# haasoscope_pro_power_board.net
KiCad netlist of a schematic drawn in EAGLE
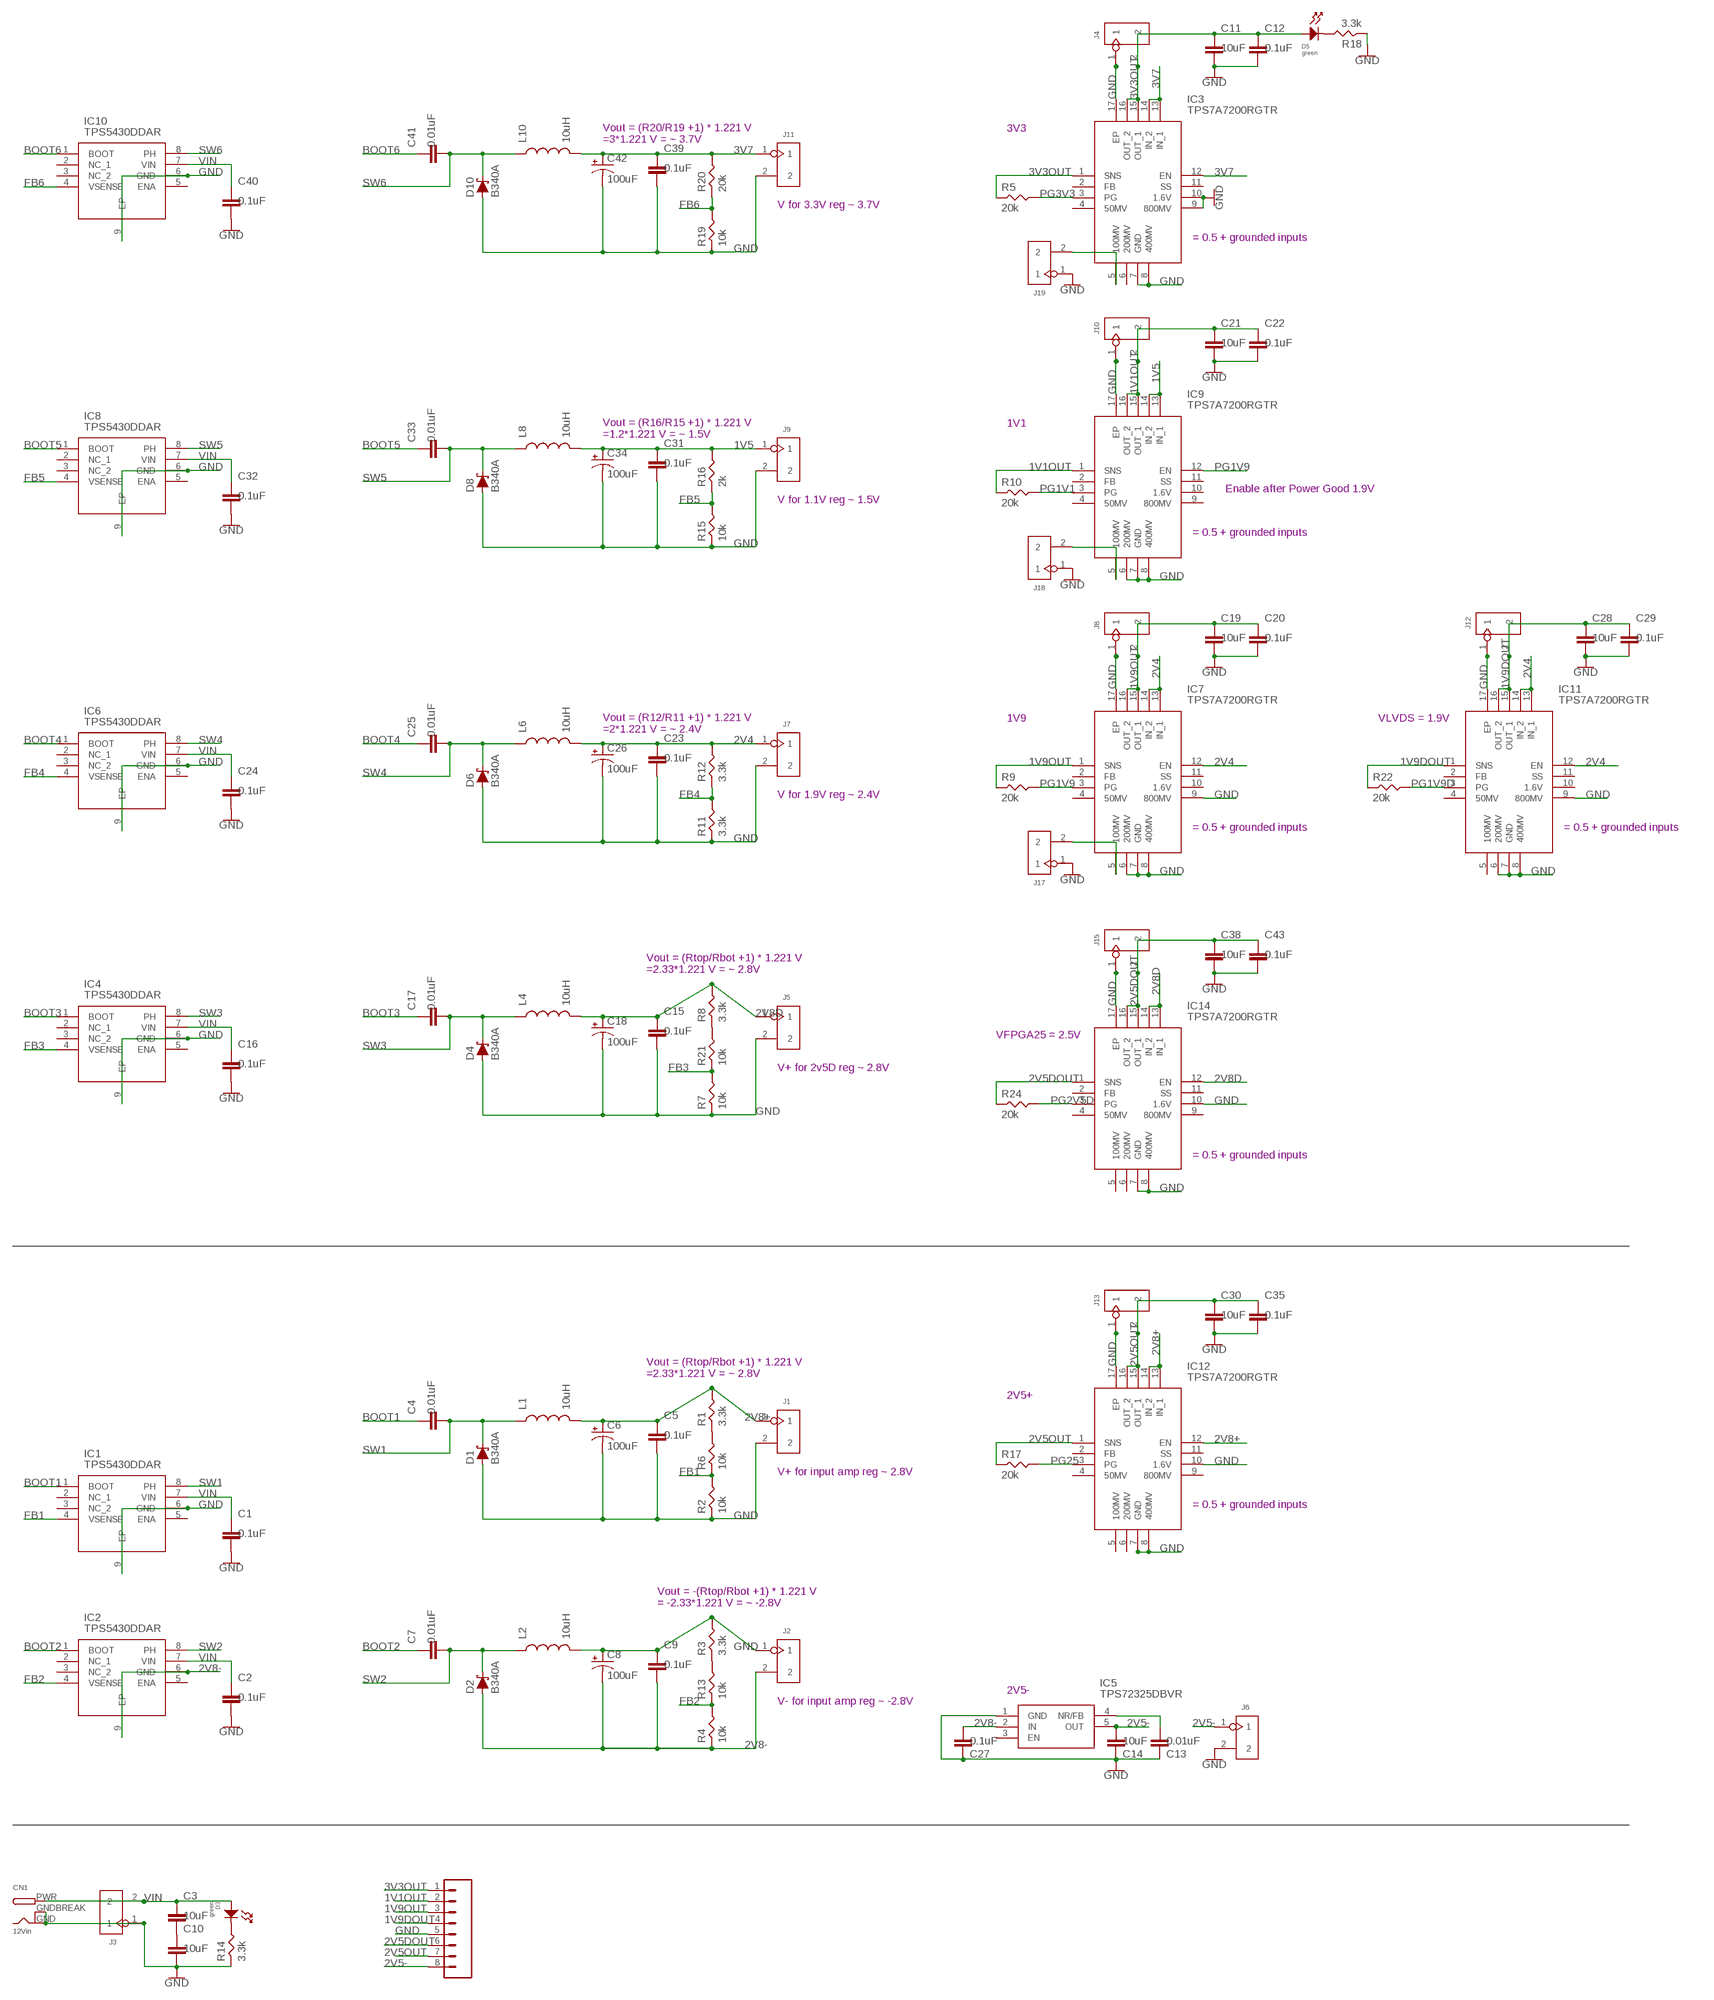
[diagram p0: schematic, sheet 1]

(export (version "E")
  (design (tool "Eeschema 10.0.6"))
  (components
    (comp (ref "C1")
      (value "0.1uF")
      (footprint "eagle-import:RESC0402_N")
      (libsource (lib "eagle-import") (part "CAPACITOR_0402_N"))
    )
    (comp (ref "C2")
      (value "0.1uF")
      (footprint "eagle-import:RESC0402_N")
      (libsource (lib "eagle-import") (part "CAPACITOR_0402_N"))
    )
    (comp (ref "C3")
      (value "10uF")
      (footprint "eagle-import:RESC0805_N")
      (libsource (lib "eagle-import") (part "CAPACITOR_0805_N"))
    )
    (comp (ref "C4")
      (value "0.01uF")
      (footprint "eagle-import:RESC0402_N")
      (libsource (lib "eagle-import") (part "CAPACITOR_0402_N"))
    )
    (comp (ref "C5")
      (value "0.1uF")
      (footprint "eagle-import:RESC0402_N")
      (libsource (lib "eagle-import") (part "CAPACITOR_0402_N"))
    )
    (comp (ref "C6")
      (value "100uF")
      (footprint "eagle-import:VISHAY_C")
      (libsource (lib "eagle-import") (part "CAP_POLSMD"))
    )
    (comp (ref "C7")
      (value "0.01uF")
      (footprint "eagle-import:RESC0402_N")
      (libsource (lib "eagle-import") (part "CAPACITOR_0402_N"))
    )
    (comp (ref "C8")
      (value "100uF")
      (footprint "eagle-import:VISHAY_C")
      (libsource (lib "eagle-import") (part "CAP_POLSMD"))
    )
    (comp (ref "C9")
      (value "0.1uF")
      (footprint "eagle-import:RESC0402_N")
      (libsource (lib "eagle-import") (part "CAPACITOR_0402_N"))
    )
    (comp (ref "C10")
      (value "10uF")
      (footprint "eagle-import:RESC0805_N")
      (libsource (lib "eagle-import") (part "CAPACITOR_0805_N"))
    )
    (comp (ref "C11")
      (value "10uF")
      (footprint "eagle-import:RESC0805_N")
      (libsource (lib "eagle-import") (part "CAPACITOR_0805_N"))
    )
    (comp (ref "C12")
      (value "0.1uF")
      (footprint "eagle-import:RESC0402_N")
      (libsource (lib "eagle-import") (part "CAPACITOR_0402_N"))
    )
    (comp (ref "C13")
      (value "0.01uF")
      (footprint "eagle-import:RESC0402_N")
      (libsource (lib "eagle-import") (part "CAPACITOR_0402_N"))
    )
    (comp (ref "C14")
      (value "10uF")
      (footprint "eagle-import:RESC0805_N")
      (libsource (lib "eagle-import") (part "CAPACITOR_0805_N"))
    )
    (comp (ref "C15")
      (value "0.1uF")
      (footprint "eagle-import:RESC0402_N")
      (libsource (lib "eagle-import") (part "CAPACITOR_0402_N"))
    )
    (comp (ref "C16")
      (value "0.1uF")
      (footprint "eagle-import:RESC0402_N")
      (libsource (lib "eagle-import") (part "CAPACITOR_0402_N"))
    )
    (comp (ref "C17")
      (value "0.01uF")
      (footprint "eagle-import:RESC0402_N")
      (libsource (lib "eagle-import") (part "CAPACITOR_0402_N"))
    )
    (comp (ref "C18")
      (value "100uF")
      (footprint "eagle-import:VISHAY_C")
      (libsource (lib "eagle-import") (part "CAP_POLSMD"))
    )
    (comp (ref "C19")
      (value "10uF")
      (footprint "eagle-import:RESC0805_N")
      (libsource (lib "eagle-import") (part "CAPACITOR_0805_N"))
    )
    (comp (ref "C20")
      (value "0.1uF")
      (footprint "eagle-import:RESC0402_N")
      (libsource (lib "eagle-import") (part "CAPACITOR_0402_N"))
    )
    (comp (ref "C21")
      (value "10uF")
      (footprint "eagle-import:RESC0805_N")
      (libsource (lib "eagle-import") (part "CAPACITOR_0805_N"))
    )
    (comp (ref "C22")
      (value "0.1uF")
      (footprint "eagle-import:RESC0402_N")
      (libsource (lib "eagle-import") (part "CAPACITOR_0402_N"))
    )
    (comp (ref "C23")
      (value "0.1uF")
      (footprint "eagle-import:RESC0402_N")
      (libsource (lib "eagle-import") (part "CAPACITOR_0402_N"))
    )
    (comp (ref "C24")
      (value "0.1uF")
      (footprint "eagle-import:RESC0402_N")
      (libsource (lib "eagle-import") (part "CAPACITOR_0402_N"))
    )
    (comp (ref "C25")
      (value "0.01uF")
      (footprint "eagle-import:RESC0402_N")
      (libsource (lib "eagle-import") (part "CAPACITOR_0402_N"))
    )
    (comp (ref "C26")
      (value "100uF")
      (footprint "eagle-import:VISHAY_C")
      (libsource (lib "eagle-import") (part "CAP_POLSMD"))
    )
    (comp (ref "C27")
      (value "0.1uF")
      (footprint "eagle-import:RESC0402_N")
      (libsource (lib "eagle-import") (part "CAPACITOR_0402_N"))
    )
    (comp (ref "C28")
      (value "10uF")
      (footprint "eagle-import:RESC0805_N")
      (libsource (lib "eagle-import") (part "CAPACITOR_0805_N"))
    )
    (comp (ref "C29")
      (value "0.1uF")
      (footprint "eagle-import:RESC0402_N")
      (libsource (lib "eagle-import") (part "CAPACITOR_0402_N"))
    )
    (comp (ref "C30")
      (value "10uF")
      (footprint "eagle-import:RESC0805_N")
      (libsource (lib "eagle-import") (part "CAPACITOR_0805_N"))
    )
    (comp (ref "C31")
      (value "0.1uF")
      (footprint "eagle-import:RESC0402_N")
      (libsource (lib "eagle-import") (part "CAPACITOR_0402_N"))
    )
    (comp (ref "C32")
      (value "0.1uF")
      (footprint "eagle-import:RESC0402_N")
      (libsource (lib "eagle-import") (part "CAPACITOR_0402_N"))
    )
    (comp (ref "C33")
      (value "0.01uF")
      (footprint "eagle-import:RESC0402_N")
      (libsource (lib "eagle-import") (part "CAPACITOR_0402_N"))
    )
    (comp (ref "C34")
      (value "100uF")
      (footprint "eagle-import:VISHAY_C")
      (libsource (lib "eagle-import") (part "CAP_POLSMD"))
    )
    (comp (ref "C35")
      (value "0.1uF")
      (footprint "eagle-import:RESC0402_N")
      (libsource (lib "eagle-import") (part "CAPACITOR_0402_N"))
    )
    (comp (ref "C38")
      (value "10uF")
      (footprint "eagle-import:RESC0805_N")
      (libsource (lib "eagle-import") (part "CAPACITOR_0805_N"))
    )
    (comp (ref "C39")
      (value "0.1uF")
      (footprint "eagle-import:RESC0402_N")
      (libsource (lib "eagle-import") (part "CAPACITOR_0402_N"))
    )
    (comp (ref "C40")
      (value "0.1uF")
      (footprint "eagle-import:RESC0402_N")
      (libsource (lib "eagle-import") (part "CAPACITOR_0402_N"))
    )
    (comp (ref "C41")
      (value "0.01uF")
      (footprint "eagle-import:RESC0402_N")
      (libsource (lib "eagle-import") (part "CAPACITOR_0402_N"))
    )
    (comp (ref "C42")
      (value "100uF")
      (footprint "eagle-import:VISHAY_C")
      (libsource (lib "eagle-import") (part "CAP_POLSMD"))
    )
    (comp (ref "C43")
      (value "0.1uF")
      (footprint "eagle-import:RESC0402_N")
      (libsource (lib "eagle-import") (part "CAPACITOR_0402_N"))
    )
    (comp (ref "CN1")
      (value "12Vin")
      (footprint "eagle-import:DCJACK_2MM_PTH")
      (libsource (lib "eagle-import") (part "DCBARRELPTH"))
    )
    (comp (ref "D1")
      (value "B340A")
      (footprint "eagle-import:SMA-DIODE")
      (libsource (lib "eagle-import") (part "DIODE-SCHOTTKY-B340A"))
    )
    (comp (ref "D2")
      (value "B340A")
      (footprint "eagle-import:SMA-DIODE")
      (libsource (lib "eagle-import") (part "DIODE-SCHOTTKY-B340A"))
    )
    (comp (ref "D3")
      (value "green")
      (footprint "eagle-import:LED0805")
      (fields (field (name "HOUSEPART") "NO"))
      (libsource (lib "eagle-import") (part "LED_SINGLE-0805"))
    )
    (comp (ref "D4")
      (value "B340A")
      (footprint "eagle-import:SMA-DIODE")
      (libsource (lib "eagle-import") (part "DIODE-SCHOTTKY-B340A"))
    )
    (comp (ref "D5")
      (value "green")
      (footprint "eagle-import:LED0805")
      (fields (field (name "HOUSEPART") "NO"))
      (libsource (lib "eagle-import") (part "LED_SINGLE-0805"))
    )
    (comp (ref "D6")
      (value "B340A")
      (footprint "eagle-import:SMA-DIODE")
      (libsource (lib "eagle-import") (part "DIODE-SCHOTTKY-B340A"))
    )
    (comp (ref "D8")
      (value "B340A")
      (footprint "eagle-import:SMA-DIODE")
      (libsource (lib "eagle-import") (part "DIODE-SCHOTTKY-B340A"))
    )
    (comp (ref "D10")
      (value "B340A")
      (footprint "eagle-import:SMA-DIODE")
      (libsource (lib "eagle-import") (part "DIODE-SCHOTTKY-B340A"))
    )
    (comp (ref "IC1")
      (value "TPS5430DDAR")
      (footprint "eagle-import:SOIC127P600X170-9N")
      (fields (field (name "MOUSER_PART_NUMBER") "595-TPS5430DDAR"))
      (libsource (lib "eagle-import") (part "TPS5430DDAR"))
    )
    (comp (ref "IC2")
      (value "TPS5430DDAR")
      (footprint "eagle-import:SOIC127P600X170-9N")
      (fields (field (name "MOUSER_PART_NUMBER") "595-TPS5430DDAR"))
      (libsource (lib "eagle-import") (part "TPS5430DDAR"))
    )
    (comp (ref "IC3")
      (value "TPS7A7200RGTR")
      (footprint "eagle-import:QFN50P300X300X100-17N")
      (fields (field (name "MOUSER_PART_NUMBER") "595-TPS7A7200RGTR"))
      (libsource (lib "eagle-import") (part "TPS7A7200RGTR"))
    )
    (comp (ref "IC4")
      (value "TPS5430DDAR")
      (footprint "eagle-import:SOIC127P600X170-9N")
      (fields (field (name "MOUSER_PART_NUMBER") "595-TPS5430DDAR"))
      (libsource (lib "eagle-import") (part "TPS5430DDAR"))
    )
    (comp (ref "IC5")
      (value "TPS72325DBVR")
      (footprint "eagle-import:SOT95P280X145-5N")
      (fields (field (name "MOUSER_PART_NUMBER") "595-TPS72325DBVR"))
      (libsource (lib "eagle-import") (part "TPS72325DBVR"))
    )
    (comp (ref "IC6")
      (value "TPS5430DDAR")
      (footprint "eagle-import:SOIC127P600X170-9N")
      (fields (field (name "MOUSER_PART_NUMBER") "595-TPS5430DDAR"))
      (libsource (lib "eagle-import") (part "TPS5430DDAR"))
    )
    (comp (ref "IC7")
      (value "TPS7A7200RGTR")
      (footprint "eagle-import:QFN50P300X300X100-17N")
      (fields (field (name "MOUSER_PART_NUMBER") "595-TPS7A7200RGTR"))
      (libsource (lib "eagle-import") (part "TPS7A7200RGTR"))
    )
    (comp (ref "IC8")
      (value "TPS5430DDAR")
      (footprint "eagle-import:SOIC127P600X170-9N")
      (fields (field (name "MOUSER_PART_NUMBER") "595-TPS5430DDAR"))
      (libsource (lib "eagle-import") (part "TPS5430DDAR"))
    )
    (comp (ref "IC9")
      (value "TPS7A7200RGTR")
      (footprint "eagle-import:QFN50P300X300X100-17N")
      (fields (field (name "MOUSER_PART_NUMBER") "595-TPS7A7200RGTR"))
      (libsource (lib "eagle-import") (part "TPS7A7200RGTR"))
    )
    (comp (ref "IC10")
      (value "TPS5430DDAR")
      (footprint "eagle-import:SOIC127P600X170-9N")
      (fields (field (name "MOUSER_PART_NUMBER") "595-TPS5430DDAR"))
      (libsource (lib "eagle-import") (part "TPS5430DDAR"))
    )
    (comp (ref "IC11")
      (value "TPS7A7200RGTR")
      (footprint "eagle-import:QFN50P300X300X100-17N")
      (fields (field (name "MOUSER_PART_NUMBER") "595-TPS7A7200RGTR"))
      (libsource (lib "eagle-import") (part "TPS7A7200RGTR"))
    )
    (comp (ref "IC12")
      (value "TPS7A7200RGTR")
      (footprint "eagle-import:QFN50P300X300X100-17N")
      (fields (field (name "MOUSER_PART_NUMBER") "595-TPS7A7200RGTR"))
      (libsource (lib "eagle-import") (part "TPS7A7200RGTR"))
    )
    (comp (ref "IC14")
      (value "TPS7A7200RGTR")
      (footprint "eagle-import:QFN50P300X300X100-17N")
      (fields (field (name "MOUSER_PART_NUMBER") "595-TPS7A7200RGTR"))
      (libsource (lib "eagle-import") (part "TPS7A7200RGTR"))
    )
    (comp (ref "J1")
      (value "2p-2.54")
      (footprint "eagle-import:H2-2.54")
      (fields (field (name "MPN") "P125-1102A0BS116A1"))
      (libsource (lib "eagle-import") (part "DIP-BLACK-MALE-HEADER-VERT(2P-2.54)"))
    )
    (comp (ref "J2")
      (value "2p-2.54")
      (footprint "eagle-import:H2-2.54")
      (fields (field (name "MPN") "P125-1102A0BS116A1"))
      (libsource (lib "eagle-import") (part "DIP-BLACK-MALE-HEADER-VERT(2P-2.54)"))
    )
    (comp (ref "J3")
      (value "2p-2.54")
      (footprint "eagle-import:H2-2.54")
      (fields (field (name "MPN") "P125-1102A0BS116A1"))
      (libsource (lib "eagle-import") (part "DIP-BLACK-MALE-HEADER-VERT(2P-2.54)"))
    )
    (comp (ref "J4")
      (value "2p-2.54")
      (footprint "eagle-import:H2-2.54")
      (fields (field (name "MPN") "P125-1102A0BS116A1"))
      (libsource (lib "eagle-import") (part "DIP-BLACK-MALE-HEADER-VERT(2P-2.54)"))
    )
    (comp (ref "J5")
      (value "2p-2.54")
      (footprint "eagle-import:H2-2.54")
      (fields (field (name "MPN") "P125-1102A0BS116A1"))
      (libsource (lib "eagle-import") (part "DIP-BLACK-MALE-HEADER-VERT(2P-2.54)"))
    )
    (comp (ref "J6")
      (value "2p-2.54")
      (footprint "eagle-import:H2-2.54")
      (fields (field (name "MPN") "P125-1102A0BS116A1"))
      (libsource (lib "eagle-import") (part "DIP-BLACK-MALE-HEADER-VERT(2P-2.54)"))
    )
    (comp (ref "J7")
      (value "2p-2.54")
      (footprint "eagle-import:H2-2.54")
      (fields (field (name "MPN") "P125-1102A0BS116A1"))
      (libsource (lib "eagle-import") (part "DIP-BLACK-MALE-HEADER-VERT(2P-2.54)"))
    )
    (comp (ref "J8")
      (value "2p-2.54")
      (footprint "eagle-import:H2-2.54")
      (fields (field (name "MPN") "P125-1102A0BS116A1"))
      (libsource (lib "eagle-import") (part "DIP-BLACK-MALE-HEADER-VERT(2P-2.54)"))
    )
    (comp (ref "J9")
      (value "2p-2.54")
      (footprint "eagle-import:H2-2.54")
      (fields (field (name "MPN") "P125-1102A0BS116A1"))
      (libsource (lib "eagle-import") (part "DIP-BLACK-MALE-HEADER-VERT(2P-2.54)"))
    )
    (comp (ref "J10")
      (value "2p-2.54")
      (footprint "eagle-import:H2-2.54")
      (fields (field (name "MPN") "P125-1102A0BS116A1"))
      (libsource (lib "eagle-import") (part "DIP-BLACK-MALE-HEADER-VERT(2P-2.54)"))
    )
    (comp (ref "J11")
      (value "2p-2.54")
      (footprint "eagle-import:H2-2.54")
      (fields (field (name "MPN") "P125-1102A0BS116A1"))
      (libsource (lib "eagle-import") (part "DIP-BLACK-MALE-HEADER-VERT(2P-2.54)"))
    )
    (comp (ref "J12")
      (value "2p-2.54")
      (footprint "eagle-import:H2-2.54")
      (fields (field (name "MPN") "P125-1102A0BS116A1"))
      (libsource (lib "eagle-import") (part "DIP-BLACK-MALE-HEADER-VERT(2P-2.54)"))
    )
    (comp (ref "J13")
      (value "2p-2.54")
      (footprint "eagle-import:H2-2.54")
      (fields (field (name "MPN") "P125-1102A0BS116A1"))
      (libsource (lib "eagle-import") (part "DIP-BLACK-MALE-HEADER-VERT(2P-2.54)"))
    )
    (comp (ref "J15")
      (value "2p-2.54")
      (footprint "eagle-import:H2-2.54")
      (fields (field (name "MPN") "P125-1102A0BS116A1"))
      (libsource (lib "eagle-import") (part "DIP-BLACK-MALE-HEADER-VERT(2P-2.54)"))
    )
    (comp (ref "J16")
      (value "8pin")
      (footprint "eagle-import:1X08")
      (libsource (lib "eagle-import") (part "CONN_08{dblquote}"))
    )
    (comp (ref "J17")
      (value "2p-2.54")
      (footprint "eagle-import:H2-2.54")
      (fields (field (name "MPN") "P125-1102A0BS116A1"))
      (libsource (lib "eagle-import") (part "DIP-BLACK-MALE-HEADER-VERT(2P-2.54)"))
    )
    (comp (ref "J18")
      (value "2p-2.54")
      (footprint "eagle-import:H2-2.54")
      (fields (field (name "MPN") "P125-1102A0BS116A1"))
      (libsource (lib "eagle-import") (part "DIP-BLACK-MALE-HEADER-VERT(2P-2.54)"))
    )
    (comp (ref "J19")
      (value "2p-2.54")
      (footprint "eagle-import:H2-2.54")
      (fields (field (name "MPN") "P125-1102A0BS116A1"))
      (libsource (lib "eagle-import") (part "DIP-BLACK-MALE-HEADER-VERT(2P-2.54)"))
    )
    (comp (ref "L1")
      (value "10uH")
      (footprint "eagle-import:CDRH125")
      (libsource (lib "eagle-import") (part "INDUCTORPWR"))
    )
    (comp (ref "L2")
      (value "10uH")
      (footprint "eagle-import:CDRH125")
      (libsource (lib "eagle-import") (part "INDUCTORPWR"))
    )
    (comp (ref "L4")
      (value "10uH")
      (footprint "eagle-import:CDRH125")
      (libsource (lib "eagle-import") (part "INDUCTORPWR"))
    )
    (comp (ref "L6")
      (value "10uH")
      (footprint "eagle-import:CDRH125")
      (libsource (lib "eagle-import") (part "INDUCTORPWR"))
    )
    (comp (ref "L8")
      (value "10uH")
      (footprint "eagle-import:CDRH125")
      (libsource (lib "eagle-import") (part "INDUCTORPWR"))
    )
    (comp (ref "L10")
      (value "10uH")
      (footprint "eagle-import:CDRH125")
      (libsource (lib "eagle-import") (part "INDUCTORPWR"))
    )
    (comp (ref "R1")
      (value "3.3k")
      (footprint "eagle-import:RES-0402")
      (libsource (lib "eagle-import") (part "RES-0402"))
    )
    (comp (ref "R2")
      (value "10k")
      (footprint "eagle-import:RES-0402")
      (libsource (lib "eagle-import") (part "RES-0402"))
    )
    (comp (ref "R3")
      (value "3.3k")
      (footprint "eagle-import:RES-0402")
      (libsource (lib "eagle-import") (part "RES-0402"))
    )
    (comp (ref "R4")
      (value "10k")
      (footprint "eagle-import:RES-0402")
      (libsource (lib "eagle-import") (part "RES-0402"))
    )
    (comp (ref "R5")
      (value "20k")
      (footprint "eagle-import:RES-0402")
      (libsource (lib "eagle-import") (part "RES-0402"))
    )
    (comp (ref "R6")
      (value "10k")
      (footprint "eagle-import:RES-0402")
      (libsource (lib "eagle-import") (part "RES-0402"))
    )
    (comp (ref "R7")
      (value "10k")
      (footprint "eagle-import:RES-0402")
      (libsource (lib "eagle-import") (part "RES-0402"))
    )
    (comp (ref "R8")
      (value "3.3k")
      (footprint "eagle-import:RES-0402")
      (libsource (lib "eagle-import") (part "RES-0402"))
    )
    (comp (ref "R9")
      (value "20k")
      (footprint "eagle-import:RES-0402")
      (libsource (lib "eagle-import") (part "RES-0402"))
    )
    (comp (ref "R10")
      (value "20k")
      (footprint "eagle-import:RES-0402")
      (libsource (lib "eagle-import") (part "RES-0402"))
    )
    (comp (ref "R11")
      (value "3.3k")
      (footprint "eagle-import:RES-0402")
      (libsource (lib "eagle-import") (part "RES-0402"))
    )
    (comp (ref "R12")
      (value "3.3k")
      (footprint "eagle-import:RES-0402")
      (libsource (lib "eagle-import") (part "RES-0402"))
    )
    (comp (ref "R13")
      (value "10k")
      (footprint "eagle-import:RES-0402")
      (libsource (lib "eagle-import") (part "RES-0402"))
    )
    (comp (ref "R14")
      (value "3.3k")
      (footprint "eagle-import:RES-0402")
      (libsource (lib "eagle-import") (part "RES-0402"))
    )
    (comp (ref "R15")
      (value "10k")
      (footprint "eagle-import:RES-0402")
      (libsource (lib "eagle-import") (part "RES-0402"))
    )
    (comp (ref "R16")
      (value "2k")
      (footprint "eagle-import:RES-0402")
      (libsource (lib "eagle-import") (part "RES-0402"))
    )
    (comp (ref "R17")
      (value "20k")
      (footprint "eagle-import:RES-0402")
      (libsource (lib "eagle-import") (part "RES-0402"))
    )
    (comp (ref "R18")
      (value "3.3k")
      (footprint "eagle-import:RES-0402")
      (libsource (lib "eagle-import") (part "RES-0402"))
    )
    (comp (ref "R19")
      (value "10k")
      (footprint "eagle-import:RES-0402")
      (libsource (lib "eagle-import") (part "RES-0402"))
    )
    (comp (ref "R20")
      (value "20k")
      (footprint "eagle-import:RES-0402")
      (libsource (lib "eagle-import") (part "RES-0402"))
    )
    (comp (ref "R21")
      (value "10k")
      (footprint "eagle-import:RES-0402")
      (libsource (lib "eagle-import") (part "RES-0402"))
    )
    (comp (ref "R22")
      (value "20k")
      (footprint "eagle-import:RES-0402")
      (libsource (lib "eagle-import") (part "RES-0402"))
    )
    (comp (ref "R24")
      (value "20k")
      (footprint "eagle-import:RES-0402")
      (libsource (lib "eagle-import") (part "RES-0402"))
    )
  )
  (nets
    (net (code "1") (name "/1V1OUT") (class "Default")
      (node (ref "C21") (pin "1") (pinfunction "1_1") (pintype "passive"))
      (node (ref "C22") (pin "1") (pinfunction "1_1") (pintype "passive"))
      (node (ref "IC9") (pin "1") (pinfunction "SNS_1") (pintype "bidirectional"))
      (node (ref "IC9") (pin "15") (pinfunction "OUT_1_15") (pintype "bidirectional"))
      (node (ref "IC9") (pin "16") (pinfunction "OUT_2_16") (pintype "bidirectional"))
      (node (ref "J10") (pin "2") (pinfunction "2_2") (pintype "bidirectional"))
      (node (ref "J16") (pin "2") (pinfunction "2_2") (pintype "passive"))
      (node (ref "R10") (pin "P$1") (pinfunction "P$1_P$1") (pintype "bidirectional"))
    )
    (net (code "2") (name "/1V5") (class "Default")
      (node (ref "C31") (pin "1") (pinfunction "1_1") (pintype "passive"))
      (node (ref "C34") (pin "+") (pinfunction "+_+") (pintype "passive"))
      (node (ref "IC9") (pin "13") (pinfunction "IN_1_13") (pintype "bidirectional"))
      (node (ref "IC9") (pin "14") (pinfunction "IN_2_14") (pintype "bidirectional"))
      (node (ref "J9") (pin "1") (pinfunction "1_1") (pintype "bidirectional"))
      (node (ref "L8") (pin "2") (pinfunction "2_2") (pintype "passive"))
      (node (ref "R16") (pin "P$2") (pinfunction "P$2_P$2") (pintype "bidirectional"))
    )
    (net (code "3") (name "/1V9DOUT") (class "Default")
      (node (ref "C28") (pin "1") (pinfunction "1_1") (pintype "passive"))
      (node (ref "C29") (pin "1") (pinfunction "1_1") (pintype "passive"))
      (node (ref "IC11") (pin "1") (pinfunction "SNS_1") (pintype "bidirectional"))
      (node (ref "IC11") (pin "15") (pinfunction "OUT_1_15") (pintype "bidirectional"))
      (node (ref "IC11") (pin "16") (pinfunction "OUT_2_16") (pintype "bidirectional"))
      (node (ref "J12") (pin "2") (pinfunction "2_2") (pintype "bidirectional"))
      (node (ref "J16") (pin "4") (pinfunction "4_4") (pintype "passive"))
      (node (ref "R22") (pin "P$1") (pinfunction "P$1_P$1") (pintype "bidirectional"))
    )
    (net (code "4") (name "/1V9OUT") (class "Default")
      (node (ref "C19") (pin "1") (pinfunction "1_1") (pintype "passive"))
      (node (ref "C20") (pin "1") (pinfunction "1_1") (pintype "passive"))
      (node (ref "IC7") (pin "1") (pinfunction "SNS_1") (pintype "bidirectional"))
      (node (ref "IC7") (pin "15") (pinfunction "OUT_1_15") (pintype "bidirectional"))
      (node (ref "IC7") (pin "16") (pinfunction "OUT_2_16") (pintype "bidirectional"))
      (node (ref "J16") (pin "3") (pinfunction "3_3") (pintype "passive"))
      (node (ref "J8") (pin "2") (pinfunction "2_2") (pintype "bidirectional"))
      (node (ref "R9") (pin "P$1") (pinfunction "P$1_P$1") (pintype "bidirectional"))
    )
    (net (code "5") (name "/2V4") (class "Default")
      (node (ref "C23") (pin "1") (pinfunction "1_1") (pintype "passive"))
      (node (ref "C26") (pin "+") (pinfunction "+_+") (pintype "passive"))
      (node (ref "IC11") (pin "12") (pinfunction "EN_12") (pintype "bidirectional"))
      (node (ref "IC11") (pin "13") (pinfunction "IN_1_13") (pintype "bidirectional"))
      (node (ref "IC11") (pin "14") (pinfunction "IN_2_14") (pintype "bidirectional"))
      (node (ref "IC7") (pin "12") (pinfunction "EN_12") (pintype "bidirectional"))
      (node (ref "IC7") (pin "13") (pinfunction "IN_1_13") (pintype "bidirectional"))
      (node (ref "IC7") (pin "14") (pinfunction "IN_2_14") (pintype "bidirectional"))
      (node (ref "J7") (pin "1") (pinfunction "1_1") (pintype "bidirectional"))
      (node (ref "L6") (pin "2") (pinfunction "2_2") (pintype "passive"))
      (node (ref "R12") (pin "P$2") (pinfunction "P$2_P$2") (pintype "bidirectional"))
    )
    (net (code "6") (name "/2V5-") (class "Default")
      (node (ref "C14") (pin "1") (pinfunction "1_1") (pintype "passive"))
      (node (ref "IC5") (pin "5") (pinfunction "OUT_5") (pintype "bidirectional"))
      (node (ref "J16") (pin "8") (pinfunction "8_8") (pintype "passive"))
      (node (ref "J6") (pin "1") (pinfunction "1_1") (pintype "bidirectional"))
    )
    (net (code "7") (name "/2V5DOUT") (class "Default")
      (node (ref "C38") (pin "1") (pinfunction "1_1") (pintype "passive"))
      (node (ref "C43") (pin "1") (pinfunction "1_1") (pintype "passive"))
      (node (ref "IC14") (pin "1") (pinfunction "SNS_1") (pintype "bidirectional"))
      (node (ref "IC14") (pin "15") (pinfunction "OUT_1_15") (pintype "bidirectional"))
      (node (ref "IC14") (pin "16") (pinfunction "OUT_2_16") (pintype "bidirectional"))
      (node (ref "J15") (pin "2") (pinfunction "2_2") (pintype "bidirectional"))
      (node (ref "J16") (pin "6") (pinfunction "6_6") (pintype "passive"))
      (node (ref "R24") (pin "P$1") (pinfunction "P$1_P$1") (pintype "bidirectional"))
    )
    (net (code "8") (name "/2V5OUT") (class "Default")
      (node (ref "C30") (pin "1") (pinfunction "1_1") (pintype "passive"))
      (node (ref "C35") (pin "1") (pinfunction "1_1") (pintype "passive"))
      (node (ref "IC12") (pin "1") (pinfunction "SNS_1") (pintype "bidirectional"))
      (node (ref "IC12") (pin "15") (pinfunction "OUT_1_15") (pintype "bidirectional"))
      (node (ref "IC12") (pin "16") (pinfunction "OUT_2_16") (pintype "bidirectional"))
      (node (ref "J13") (pin "2") (pinfunction "2_2") (pintype "bidirectional"))
      (node (ref "J16") (pin "7") (pinfunction "7_7") (pintype "passive"))
      (node (ref "R17") (pin "P$1") (pinfunction "P$1_P$1") (pintype "bidirectional"))
    )
    (net (code "9") (name "/2V8+") (class "Default")
      (node (ref "C5") (pin "1") (pinfunction "1_1") (pintype "passive"))
      (node (ref "C6") (pin "+") (pinfunction "+_+") (pintype "passive"))
      (node (ref "IC12") (pin "12") (pinfunction "EN_12") (pintype "bidirectional"))
      (node (ref "IC12") (pin "13") (pinfunction "IN_1_13") (pintype "bidirectional"))
      (node (ref "IC12") (pin "14") (pinfunction "IN_2_14") (pintype "bidirectional"))
      (node (ref "J1") (pin "1") (pinfunction "1_1") (pintype "bidirectional"))
      (node (ref "L1") (pin "2") (pinfunction "2_2") (pintype "passive"))
      (node (ref "R1") (pin "P$2") (pinfunction "P$2_P$2") (pintype "bidirectional"))
    )
    (net (code "10") (name "/2V8-") (class "Default")
      (node (ref "C27") (pin "1") (pinfunction "1_1") (pintype "passive"))
      (node (ref "C8") (pin "-") (pinfunction "-_-") (pintype "passive"))
      (node (ref "C9") (pin "2") (pinfunction "2_2") (pintype "passive"))
      (node (ref "D2") (pin "A") (pinfunction "A_A") (pintype "passive"))
      (node (ref "IC2") (pin "6") (pinfunction "GND_6") (pintype "bidirectional"))
      (node (ref "IC2") (pin "9") (pinfunction "EP_9") (pintype "bidirectional"))
      (node (ref "IC5") (pin "2") (pinfunction "IN_2") (pintype "bidirectional"))
      (node (ref "J2") (pin "2") (pinfunction "2_2") (pintype "bidirectional"))
      (node (ref "R4") (pin "P$1") (pinfunction "P$1_P$1") (pintype "bidirectional"))
    )
    (net (code "11") (name "/2V8D") (class "Default")
      (node (ref "C15") (pin "1") (pinfunction "1_1") (pintype "passive"))
      (node (ref "C18") (pin "+") (pinfunction "+_+") (pintype "passive"))
      (node (ref "IC14") (pin "12") (pinfunction "EN_12") (pintype "bidirectional"))
      (node (ref "IC14") (pin "13") (pinfunction "IN_1_13") (pintype "bidirectional"))
      (node (ref "IC14") (pin "14") (pinfunction "IN_2_14") (pintype "bidirectional"))
      (node (ref "J5") (pin "1") (pinfunction "1_1") (pintype "bidirectional"))
      (node (ref "L4") (pin "2") (pinfunction "2_2") (pintype "passive"))
      (node (ref "R8") (pin "P$2") (pinfunction "P$2_P$2") (pintype "bidirectional"))
    )
    (net (code "12") (name "/3V3OUT") (class "Default")
      (node (ref "C11") (pin "1") (pinfunction "1_1") (pintype "passive"))
      (node (ref "C12") (pin "1") (pinfunction "1_1") (pintype "passive"))
      (node (ref "D5") (pin "ANODE") (pinfunction "ANODE_ANODE") (pintype "power_in"))
      (node (ref "IC3") (pin "1") (pinfunction "SNS_1") (pintype "bidirectional"))
      (node (ref "IC3") (pin "15") (pinfunction "OUT_1_15") (pintype "bidirectional"))
      (node (ref "IC3") (pin "16") (pinfunction "OUT_2_16") (pintype "bidirectional"))
      (node (ref "J16") (pin "1") (pinfunction "1_1") (pintype "passive"))
      (node (ref "J4") (pin "2") (pinfunction "2_2") (pintype "bidirectional"))
      (node (ref "R5") (pin "P$1") (pinfunction "P$1_P$1") (pintype "bidirectional"))
    )
    (net (code "13") (name "/3V7") (class "Default")
      (node (ref "C39") (pin "1") (pinfunction "1_1") (pintype "passive"))
      (node (ref "C42") (pin "+") (pinfunction "+_+") (pintype "passive"))
      (node (ref "IC3") (pin "12") (pinfunction "EN_12") (pintype "bidirectional"))
      (node (ref "IC3") (pin "13") (pinfunction "IN_1_13") (pintype "bidirectional"))
      (node (ref "IC3") (pin "14") (pinfunction "IN_2_14") (pintype "bidirectional"))
      (node (ref "J11") (pin "1") (pinfunction "1_1") (pintype "bidirectional"))
      (node (ref "L10") (pin "2") (pinfunction "2_2") (pintype "passive"))
      (node (ref "R20") (pin "P$2") (pinfunction "P$2_P$2") (pintype "bidirectional"))
    )
    (net (code "14") (name "/BOOT1") (class "Default")
      (node (ref "C4") (pin "1") (pinfunction "1_1") (pintype "passive"))
      (node (ref "IC1") (pin "1") (pinfunction "BOOT_1") (pintype "bidirectional"))
    )
    (net (code "15") (name "/BOOT2") (class "Default")
      (node (ref "C7") (pin "1") (pinfunction "1_1") (pintype "passive"))
      (node (ref "IC2") (pin "1") (pinfunction "BOOT_1") (pintype "bidirectional"))
    )
    (net (code "16") (name "/BOOT3") (class "Default")
      (node (ref "C17") (pin "1") (pinfunction "1_1") (pintype "passive"))
      (node (ref "IC4") (pin "1") (pinfunction "BOOT_1") (pintype "bidirectional"))
    )
    (net (code "17") (name "/BOOT4") (class "Default")
      (node (ref "C25") (pin "1") (pinfunction "1_1") (pintype "passive"))
      (node (ref "IC6") (pin "1") (pinfunction "BOOT_1") (pintype "bidirectional"))
    )
    (net (code "18") (name "/BOOT5") (class "Default")
      (node (ref "C33") (pin "1") (pinfunction "1_1") (pintype "passive"))
      (node (ref "IC8") (pin "1") (pinfunction "BOOT_1") (pintype "bidirectional"))
    )
    (net (code "19") (name "/BOOT6") (class "Default")
      (node (ref "C41") (pin "1") (pinfunction "1_1") (pintype "passive"))
      (node (ref "IC10") (pin "1") (pinfunction "BOOT_1") (pintype "bidirectional"))
    )
    (net (code "20") (name "/FB1") (class "Default")
      (node (ref "IC1") (pin "4") (pinfunction "VSENSE_4") (pintype "bidirectional"))
      (node (ref "R2") (pin "P$2") (pinfunction "P$2_P$2") (pintype "bidirectional"))
      (node (ref "R6") (pin "P$1") (pinfunction "P$1_P$1") (pintype "bidirectional"))
    )
    (net (code "21") (name "/FB2") (class "Default")
      (node (ref "IC2") (pin "4") (pinfunction "VSENSE_4") (pintype "bidirectional"))
      (node (ref "R13") (pin "P$1") (pinfunction "P$1_P$1") (pintype "bidirectional"))
      (node (ref "R4") (pin "P$2") (pinfunction "P$2_P$2") (pintype "bidirectional"))
    )
    (net (code "22") (name "/FB3") (class "Default")
      (node (ref "IC4") (pin "4") (pinfunction "VSENSE_4") (pintype "bidirectional"))
      (node (ref "R21") (pin "P$1") (pinfunction "P$1_P$1") (pintype "bidirectional"))
      (node (ref "R7") (pin "P$2") (pinfunction "P$2_P$2") (pintype "bidirectional"))
    )
    (net (code "23") (name "/FB4") (class "Default")
      (node (ref "IC6") (pin "4") (pinfunction "VSENSE_4") (pintype "bidirectional"))
      (node (ref "R11") (pin "P$2") (pinfunction "P$2_P$2") (pintype "bidirectional"))
      (node (ref "R12") (pin "P$1") (pinfunction "P$1_P$1") (pintype "bidirectional"))
    )
    (net (code "24") (name "/FB5") (class "Default")
      (node (ref "IC8") (pin "4") (pinfunction "VSENSE_4") (pintype "bidirectional"))
      (node (ref "R15") (pin "P$2") (pinfunction "P$2_P$2") (pintype "bidirectional"))
      (node (ref "R16") (pin "P$1") (pinfunction "P$1_P$1") (pintype "bidirectional"))
    )
    (net (code "25") (name "/FB6") (class "Default")
      (node (ref "IC10") (pin "4") (pinfunction "VSENSE_4") (pintype "bidirectional"))
      (node (ref "R19") (pin "P$2") (pinfunction "P$2_P$2") (pintype "bidirectional"))
      (node (ref "R20") (pin "P$1") (pinfunction "P$1_P$1") (pintype "bidirectional"))
    )
    (net (code "26") (name "/PG1V1") (class "Default")
      (node (ref "IC9") (pin "3") (pinfunction "PG_3") (pintype "bidirectional"))
      (node (ref "R10") (pin "P$2") (pinfunction "P$2_P$2") (pintype "bidirectional"))
    )
    (net (code "27") (name "/PG1V9") (class "Default")
      (node (ref "IC7") (pin "3") (pinfunction "PG_3") (pintype "bidirectional"))
      (node (ref "IC9") (pin "12") (pinfunction "EN_12") (pintype "bidirectional"))
      (node (ref "R9") (pin "P$2") (pinfunction "P$2_P$2") (pintype "bidirectional"))
    )
    (net (code "28") (name "/PG1V9D") (class "Default")
      (node (ref "IC11") (pin "3") (pinfunction "PG_3") (pintype "bidirectional"))
      (node (ref "R22") (pin "P$2") (pinfunction "P$2_P$2") (pintype "bidirectional"))
    )
    (net (code "29") (name "/PG2V5D") (class "Default")
      (node (ref "IC14") (pin "3") (pinfunction "PG_3") (pintype "bidirectional"))
      (node (ref "R24") (pin "P$2") (pinfunction "P$2_P$2") (pintype "bidirectional"))
    )
    (net (code "30") (name "/PG3V3") (class "Default")
      (node (ref "IC3") (pin "3") (pinfunction "PG_3") (pintype "bidirectional"))
      (node (ref "R5") (pin "P$2") (pinfunction "P$2_P$2") (pintype "bidirectional"))
    )
    (net (code "31") (name "/PG25") (class "Default")
      (node (ref "IC12") (pin "3") (pinfunction "PG_3") (pintype "bidirectional"))
      (node (ref "R17") (pin "P$2") (pinfunction "P$2_P$2") (pintype "bidirectional"))
    )
    (net (code "32") (name "/SW1") (class "Default")
      (node (ref "C4") (pin "2") (pinfunction "2_2") (pintype "passive"))
      (node (ref "D1") (pin "C") (pinfunction "C_C") (pintype "passive"))
      (node (ref "IC1") (pin "8") (pinfunction "PH_8") (pintype "bidirectional"))
      (node (ref "L1") (pin "1") (pinfunction "1_1") (pintype "passive"))
    )
    (net (code "33") (name "/SW2") (class "Default")
      (node (ref "C7") (pin "2") (pinfunction "2_2") (pintype "passive"))
      (node (ref "D2") (pin "C") (pinfunction "C_C") (pintype "passive"))
      (node (ref "IC2") (pin "8") (pinfunction "PH_8") (pintype "bidirectional"))
      (node (ref "L2") (pin "1") (pinfunction "1_1") (pintype "passive"))
    )
    (net (code "34") (name "/SW3") (class "Default")
      (node (ref "C17") (pin "2") (pinfunction "2_2") (pintype "passive"))
      (node (ref "D4") (pin "C") (pinfunction "C_C") (pintype "passive"))
      (node (ref "IC4") (pin "8") (pinfunction "PH_8") (pintype "bidirectional"))
      (node (ref "L4") (pin "1") (pinfunction "1_1") (pintype "passive"))
    )
    (net (code "35") (name "/SW4") (class "Default")
      (node (ref "C25") (pin "2") (pinfunction "2_2") (pintype "passive"))
      (node (ref "D6") (pin "C") (pinfunction "C_C") (pintype "passive"))
      (node (ref "IC6") (pin "8") (pinfunction "PH_8") (pintype "bidirectional"))
      (node (ref "L6") (pin "1") (pinfunction "1_1") (pintype "passive"))
    )
    (net (code "36") (name "/SW5") (class "Default")
      (node (ref "C33") (pin "2") (pinfunction "2_2") (pintype "passive"))
      (node (ref "D8") (pin "C") (pinfunction "C_C") (pintype "passive"))
      (node (ref "IC8") (pin "8") (pinfunction "PH_8") (pintype "bidirectional"))
      (node (ref "L8") (pin "1") (pinfunction "1_1") (pintype "passive"))
    )
    (net (code "37") (name "/SW6") (class "Default")
      (node (ref "C41") (pin "2") (pinfunction "2_2") (pintype "passive"))
      (node (ref "D10") (pin "C") (pinfunction "C_C") (pintype "passive"))
      (node (ref "IC10") (pin "8") (pinfunction "PH_8") (pintype "bidirectional"))
      (node (ref "L10") (pin "1") (pinfunction "1_1") (pintype "passive"))
    )
    (net (code "38") (name "/VIN") (class "Default")
      (node (ref "C1") (pin "1") (pinfunction "1_1") (pintype "passive"))
      (node (ref "C16") (pin "1") (pinfunction "1_1") (pintype "passive"))
      (node (ref "C2") (pin "1") (pinfunction "1_1") (pintype "passive"))
      (node (ref "C24") (pin "1") (pinfunction "1_1") (pintype "passive"))
      (node (ref "C3") (pin "1") (pinfunction "1_1") (pintype "passive"))
      (node (ref "C32") (pin "1") (pinfunction "1_1") (pintype "passive"))
      (node (ref "C40") (pin "1") (pinfunction "1_1") (pintype "passive"))
      (node (ref "CN1") (pin "PWR") (pinfunction "PWR_PWR") (pintype "power_in"))
      (node (ref "D3") (pin "ANODE") (pinfunction "ANODE_ANODE") (pintype "power_in"))
      (node (ref "IC1") (pin "7") (pinfunction "VIN_7") (pintype "bidirectional"))
      (node (ref "IC10") (pin "7") (pinfunction "VIN_7") (pintype "bidirectional"))
      (node (ref "IC2") (pin "7") (pinfunction "VIN_7") (pintype "bidirectional"))
      (node (ref "IC4") (pin "7") (pinfunction "VIN_7") (pintype "bidirectional"))
      (node (ref "IC6") (pin "7") (pinfunction "VIN_7") (pintype "bidirectional"))
      (node (ref "IC8") (pin "7") (pinfunction "VIN_7") (pintype "bidirectional"))
      (node (ref "J3") (pin "2") (pinfunction "2_2") (pintype "bidirectional"))
    )
    (net (code "39") (name "GND") (class "Default")
      (node (ref "C1") (pin "2") (pinfunction "2_2") (pintype "passive"))
      (node (ref "C10") (pin "2") (pinfunction "2_2") (pintype "passive"))
      (node (ref "C11") (pin "2") (pinfunction "2_2") (pintype "passive"))
      (node (ref "C12") (pin "2") (pinfunction "2_2") (pintype "passive"))
      (node (ref "C13") (pin "2") (pinfunction "2_2") (pintype "passive"))
      (node (ref "C14") (pin "2") (pinfunction "2_2") (pintype "passive"))
      (node (ref "C15") (pin "2") (pinfunction "2_2") (pintype "passive"))
      (node (ref "C16") (pin "2") (pinfunction "2_2") (pintype "passive"))
      (node (ref "C18") (pin "-") (pinfunction "-_-") (pintype "passive"))
      (node (ref "C19") (pin "2") (pinfunction "2_2") (pintype "passive"))
      (node (ref "C2") (pin "2") (pinfunction "2_2") (pintype "passive"))
      (node (ref "C20") (pin "2") (pinfunction "2_2") (pintype "passive"))
      (node (ref "C21") (pin "2") (pinfunction "2_2") (pintype "passive"))
      (node (ref "C22") (pin "2") (pinfunction "2_2") (pintype "passive"))
      (node (ref "C23") (pin "2") (pinfunction "2_2") (pintype "passive"))
      (node (ref "C24") (pin "2") (pinfunction "2_2") (pintype "passive"))
      (node (ref "C26") (pin "-") (pinfunction "-_-") (pintype "passive"))
      (node (ref "C27") (pin "2") (pinfunction "2_2") (pintype "passive"))
      (node (ref "C28") (pin "2") (pinfunction "2_2") (pintype "passive"))
      (node (ref "C29") (pin "2") (pinfunction "2_2") (pintype "passive"))
      (node (ref "C30") (pin "2") (pinfunction "2_2") (pintype "passive"))
      (node (ref "C31") (pin "2") (pinfunction "2_2") (pintype "passive"))
      (node (ref "C32") (pin "2") (pinfunction "2_2") (pintype "passive"))
      (node (ref "C34") (pin "-") (pinfunction "-_-") (pintype "passive"))
      (node (ref "C35") (pin "2") (pinfunction "2_2") (pintype "passive"))
      (node (ref "C38") (pin "2") (pinfunction "2_2") (pintype "passive"))
      (node (ref "C39") (pin "2") (pinfunction "2_2") (pintype "passive"))
      (node (ref "C40") (pin "2") (pinfunction "2_2") (pintype "passive"))
      (node (ref "C42") (pin "-") (pinfunction "-_-") (pintype "passive"))
      (node (ref "C43") (pin "2") (pinfunction "2_2") (pintype "passive"))
      (node (ref "C5") (pin "2") (pinfunction "2_2") (pintype "passive"))
      (node (ref "C6") (pin "-") (pinfunction "-_-") (pintype "passive"))
      (node (ref "C8") (pin "+") (pinfunction "+_+") (pintype "passive"))
      (node (ref "C9") (pin "1") (pinfunction "1_1") (pintype "passive"))
      (node (ref "CN1") (pin "GND") (pinfunction "GND_GND") (pintype "power_in"))
      (node (ref "CN1") (pin "GNDBREAK") (pinfunction "GNDBREAK_GNDBREAK") (pintype "power_in"))
      (node (ref "D1") (pin "A") (pinfunction "A_A") (pintype "passive"))
      (node (ref "D10") (pin "A") (pinfunction "A_A") (pintype "passive"))
      (node (ref "D4") (pin "A") (pinfunction "A_A") (pintype "passive"))
      (node (ref "D6") (pin "A") (pinfunction "A_A") (pintype "passive"))
      (node (ref "D8") (pin "A") (pinfunction "A_A") (pintype "passive"))
      (node (ref "IC1") (pin "6") (pinfunction "GND_6") (pintype "bidirectional"))
      (node (ref "IC1") (pin "9") (pinfunction "EP_9") (pintype "bidirectional"))
      (node (ref "IC10") (pin "6") (pinfunction "GND_6") (pintype "bidirectional"))
      (node (ref "IC10") (pin "9") (pinfunction "EP_9") (pintype "bidirectional"))
      (node (ref "IC11") (pin "17") (pinfunction "EP_17") (pintype "bidirectional"))
      (node (ref "IC11") (pin "6") (pinfunction "200MV_6") (pintype "bidirectional"))
      (node (ref "IC11") (pin "7") (pinfunction "GND_7") (pintype "bidirectional"))
      (node (ref "IC11") (pin "8") (pinfunction "400MV_8") (pintype "bidirectional"))
      (node (ref "IC11") (pin "9") (pinfunction "800MV_9") (pintype "bidirectional"))
      (node (ref "IC12") (pin "10") (pinfunction "1.6V_10") (pintype "bidirectional"))
      (node (ref "IC12") (pin "17") (pinfunction "EP_17") (pintype "bidirectional"))
      (node (ref "IC12") (pin "7") (pinfunction "GND_7") (pintype "bidirectional"))
      (node (ref "IC12") (pin "8") (pinfunction "400MV_8") (pintype "bidirectional"))
      (node (ref "IC14") (pin "10") (pinfunction "1.6V_10") (pintype "bidirectional"))
      (node (ref "IC14") (pin "17") (pinfunction "EP_17") (pintype "bidirectional"))
      (node (ref "IC14") (pin "7") (pinfunction "GND_7") (pintype "bidirectional"))
      (node (ref "IC14") (pin "8") (pinfunction "400MV_8") (pintype "bidirectional"))
      (node (ref "IC3") (pin "10") (pinfunction "1.6V_10") (pintype "bidirectional"))
      (node (ref "IC3") (pin "17") (pinfunction "EP_17") (pintype "bidirectional"))
      (node (ref "IC3") (pin "7") (pinfunction "GND_7") (pintype "bidirectional"))
      (node (ref "IC3") (pin "8") (pinfunction "400MV_8") (pintype "bidirectional"))
      (node (ref "IC3") (pin "9") (pinfunction "800MV_9") (pintype "bidirectional"))
      (node (ref "IC4") (pin "6") (pinfunction "GND_6") (pintype "bidirectional"))
      (node (ref "IC4") (pin "9") (pinfunction "EP_9") (pintype "bidirectional"))
      (node (ref "IC5") (pin "1") (pinfunction "GND_1") (pintype "bidirectional"))
      (node (ref "IC6") (pin "6") (pinfunction "GND_6") (pintype "bidirectional"))
      (node (ref "IC6") (pin "9") (pinfunction "EP_9") (pintype "bidirectional"))
      (node (ref "IC7") (pin "17") (pinfunction "EP_17") (pintype "bidirectional"))
      (node (ref "IC7") (pin "6") (pinfunction "200MV_6") (pintype "bidirectional"))
      (node (ref "IC7") (pin "7") (pinfunction "GND_7") (pintype "bidirectional"))
      (node (ref "IC7") (pin "8") (pinfunction "400MV_8") (pintype "bidirectional"))
      (node (ref "IC7") (pin "9") (pinfunction "800MV_9") (pintype "bidirectional"))
      (node (ref "IC8") (pin "6") (pinfunction "GND_6") (pintype "bidirectional"))
      (node (ref "IC8") (pin "9") (pinfunction "EP_9") (pintype "bidirectional"))
      (node (ref "IC9") (pin "17") (pinfunction "EP_17") (pintype "bidirectional"))
      (node (ref "IC9") (pin "6") (pinfunction "200MV_6") (pintype "bidirectional"))
      (node (ref "IC9") (pin "7") (pinfunction "GND_7") (pintype "bidirectional"))
      (node (ref "IC9") (pin "8") (pinfunction "400MV_8") (pintype "bidirectional"))
      (node (ref "J1") (pin "2") (pinfunction "2_2") (pintype "bidirectional"))
      (node (ref "J10") (pin "1") (pinfunction "1_1") (pintype "bidirectional"))
      (node (ref "J11") (pin "2") (pinfunction "2_2") (pintype "bidirectional"))
      (node (ref "J12") (pin "1") (pinfunction "1_1") (pintype "bidirectional"))
      (node (ref "J13") (pin "1") (pinfunction "1_1") (pintype "bidirectional"))
      (node (ref "J15") (pin "1") (pinfunction "1_1") (pintype "bidirectional"))
      (node (ref "J16") (pin "5") (pinfunction "5_5") (pintype "passive"))
      (node (ref "J17") (pin "1") (pinfunction "1_1") (pintype "bidirectional"))
      (node (ref "J18") (pin "1") (pinfunction "1_1") (pintype "bidirectional"))
      (node (ref "J19") (pin "1") (pinfunction "1_1") (pintype "bidirectional"))
      (node (ref "J2") (pin "1") (pinfunction "1_1") (pintype "bidirectional"))
      (node (ref "J3") (pin "1") (pinfunction "1_1") (pintype "bidirectional"))
      (node (ref "J4") (pin "1") (pinfunction "1_1") (pintype "bidirectional"))
      (node (ref "J5") (pin "2") (pinfunction "2_2") (pintype "bidirectional"))
      (node (ref "J6") (pin "2") (pinfunction "2_2") (pintype "bidirectional"))
      (node (ref "J7") (pin "2") (pinfunction "2_2") (pintype "bidirectional"))
      (node (ref "J8") (pin "1") (pinfunction "1_1") (pintype "bidirectional"))
      (node (ref "J9") (pin "2") (pinfunction "2_2") (pintype "bidirectional"))
      (node (ref "L2") (pin "2") (pinfunction "2_2") (pintype "passive"))
      (node (ref "R11") (pin "P$1") (pinfunction "P$1_P$1") (pintype "bidirectional"))
      (node (ref "R14") (pin "P$1") (pinfunction "P$1_P$1") (pintype "bidirectional"))
      (node (ref "R15") (pin "P$1") (pinfunction "P$1_P$1") (pintype "bidirectional"))
      (node (ref "R18") (pin "P$1") (pinfunction "P$1_P$1") (pintype "bidirectional"))
      (node (ref "R19") (pin "P$1") (pinfunction "P$1_P$1") (pintype "bidirectional"))
      (node (ref "R2") (pin "P$1") (pinfunction "P$1_P$1") (pintype "bidirectional"))
      (node (ref "R3") (pin "P$2") (pinfunction "P$2_P$2") (pintype "bidirectional"))
      (node (ref "R7") (pin "P$1") (pinfunction "P$1_P$1") (pintype "bidirectional"))
    )
    (net (code "40") (name "Net-(C10-Pad1)") (class "Default")
      (node (ref "C10") (pin "1") (pinfunction "1_1") (pintype "passive"))
      (node (ref "C3") (pin "2") (pinfunction "2_2") (pintype "passive"))
    )
    (net (code "41") (name "Net-(D3-PadCATHODE)") (class "Default")
      (node (ref "D3") (pin "CATHODE") (pinfunction "CATHODE_CATHODE") (pintype "power_in"))
      (node (ref "R14") (pin "P$2") (pinfunction "P$2_P$2") (pintype "bidirectional"))
    )
    (net (code "42") (name "Net-(D5-PadCATHODE)") (class "Default")
      (node (ref "D5") (pin "CATHODE") (pinfunction "CATHODE_CATHODE") (pintype "power_in"))
      (node (ref "R18") (pin "P$2") (pinfunction "P$2_P$2") (pintype "bidirectional"))
    )
    (net (code "43") (name "Net-(IC3-100MV)") (class "Default")
      (node (ref "IC3") (pin "5") (pinfunction "100MV_5") (pintype "bidirectional"))
      (node (ref "J19") (pin "2") (pinfunction "2_2") (pintype "bidirectional"))
    )
    (net (code "44") (name "Net-(IC5-NR{slash}FB)") (class "Default")
      (node (ref "C13") (pin "1") (pinfunction "1_1") (pintype "passive"))
      (node (ref "IC5") (pin "4") (pinfunction "NR/FB_4") (pintype "bidirectional"))
    )
    (net (code "45") (name "Net-(IC7-100MV)") (class "Default")
      (node (ref "IC7") (pin "5") (pinfunction "100MV_5") (pintype "bidirectional"))
      (node (ref "J17") (pin "2") (pinfunction "2_2") (pintype "bidirectional"))
    )
    (net (code "46") (name "Net-(IC9-100MV)") (class "Default")
      (node (ref "IC9") (pin "5") (pinfunction "100MV_5") (pintype "bidirectional"))
      (node (ref "J18") (pin "2") (pinfunction "2_2") (pintype "bidirectional"))
    )
    (net (code "47") (name "Net-(R1-PadP$1)") (class "Default")
      (node (ref "R1") (pin "P$1") (pinfunction "P$1_P$1") (pintype "bidirectional"))
      (node (ref "R6") (pin "P$2") (pinfunction "P$2_P$2") (pintype "bidirectional"))
    )
    (net (code "48") (name "Net-(R13-PadP$2)") (class "Default")
      (node (ref "R13") (pin "P$2") (pinfunction "P$2_P$2") (pintype "bidirectional"))
      (node (ref "R3") (pin "P$1") (pinfunction "P$1_P$1") (pintype "bidirectional"))
    )
    (net (code "49") (name "Net-(R21-PadP$2)") (class "Default")
      (node (ref "R21") (pin "P$2") (pinfunction "P$2_P$2") (pintype "bidirectional"))
      (node (ref "R8") (pin "P$1") (pinfunction "P$1_P$1") (pintype "bidirectional"))
    )
    (net (code "50") (name "unconnected-(IC1-ENA-Pad5)") (class "Default")
      (node (ref "IC1") (pin "5") (pinfunction "ENA_5") (pintype "bidirectional"))
    )
    (net (code "51") (name "unconnected-(IC1-NC_1-Pad2)") (class "Default")
      (node (ref "IC1") (pin "2") (pinfunction "NC_1_2") (pintype "bidirectional"))
    )
    (net (code "52") (name "unconnected-(IC1-NC_2-Pad3)") (class "Default")
      (node (ref "IC1") (pin "3") (pinfunction "NC_2_3") (pintype "bidirectional"))
    )
    (net (code "53") (name "unconnected-(IC2-ENA-Pad5)") (class "Default")
      (node (ref "IC2") (pin "5") (pinfunction "ENA_5") (pintype "bidirectional"))
    )
    (net (code "54") (name "unconnected-(IC2-NC_1-Pad2)") (class "Default")
      (node (ref "IC2") (pin "2") (pinfunction "NC_1_2") (pintype "bidirectional"))
    )
    (net (code "55") (name "unconnected-(IC2-NC_2-Pad3)") (class "Default")
      (node (ref "IC2") (pin "3") (pinfunction "NC_2_3") (pintype "bidirectional"))
    )
    (net (code "56") (name "unconnected-(IC3-50MV-Pad4)") (class "Default")
      (node (ref "IC3") (pin "4") (pinfunction "50MV_4") (pintype "bidirectional"))
    )
    (net (code "57") (name "unconnected-(IC3-200MV-Pad6)") (class "Default")
      (node (ref "IC3") (pin "6") (pinfunction "200MV_6") (pintype "bidirectional"))
    )
    (net (code "58") (name "unconnected-(IC3-FB-Pad2)") (class "Default")
      (node (ref "IC3") (pin "2") (pinfunction "FB_2") (pintype "bidirectional"))
    )
    (net (code "59") (name "unconnected-(IC3-SS-Pad11)") (class "Default")
      (node (ref "IC3") (pin "11") (pinfunction "SS_11") (pintype "bidirectional"))
    )
    (net (code "60") (name "unconnected-(IC4-ENA-Pad5)") (class "Default")
      (node (ref "IC4") (pin "5") (pinfunction "ENA_5") (pintype "bidirectional"))
    )
    (net (code "61") (name "unconnected-(IC4-NC_1-Pad2)") (class "Default")
      (node (ref "IC4") (pin "2") (pinfunction "NC_1_2") (pintype "bidirectional"))
    )
    (net (code "62") (name "unconnected-(IC4-NC_2-Pad3)") (class "Default")
      (node (ref "IC4") (pin "3") (pinfunction "NC_2_3") (pintype "bidirectional"))
    )
    (net (code "63") (name "unconnected-(IC5-EN-Pad3)") (class "Default")
      (node (ref "IC5") (pin "3") (pinfunction "EN_3") (pintype "bidirectional"))
    )
    (net (code "64") (name "unconnected-(IC6-ENA-Pad5)") (class "Default")
      (node (ref "IC6") (pin "5") (pinfunction "ENA_5") (pintype "bidirectional"))
    )
    (net (code "65") (name "unconnected-(IC6-NC_1-Pad2)") (class "Default")
      (node (ref "IC6") (pin "2") (pinfunction "NC_1_2") (pintype "bidirectional"))
    )
    (net (code "66") (name "unconnected-(IC6-NC_2-Pad3)") (class "Default")
      (node (ref "IC6") (pin "3") (pinfunction "NC_2_3") (pintype "bidirectional"))
    )
    (net (code "67") (name "unconnected-(IC7-1.6V-Pad10)") (class "Default")
      (node (ref "IC7") (pin "10") (pinfunction "1.6V_10") (pintype "bidirectional"))
    )
    (net (code "68") (name "unconnected-(IC7-50MV-Pad4)") (class "Default")
      (node (ref "IC7") (pin "4") (pinfunction "50MV_4") (pintype "bidirectional"))
    )
    (net (code "69") (name "unconnected-(IC7-FB-Pad2)") (class "Default")
      (node (ref "IC7") (pin "2") (pinfunction "FB_2") (pintype "bidirectional"))
    )
    (net (code "70") (name "unconnected-(IC7-SS-Pad11)") (class "Default")
      (node (ref "IC7") (pin "11") (pinfunction "SS_11") (pintype "bidirectional"))
    )
    (net (code "71") (name "unconnected-(IC8-ENA-Pad5)") (class "Default")
      (node (ref "IC8") (pin "5") (pinfunction "ENA_5") (pintype "bidirectional"))
    )
    (net (code "72") (name "unconnected-(IC8-NC_1-Pad2)") (class "Default")
      (node (ref "IC8") (pin "2") (pinfunction "NC_1_2") (pintype "bidirectional"))
    )
    (net (code "73") (name "unconnected-(IC8-NC_2-Pad3)") (class "Default")
      (node (ref "IC8") (pin "3") (pinfunction "NC_2_3") (pintype "bidirectional"))
    )
    (net (code "74") (name "unconnected-(IC9-1.6V-Pad10)") (class "Default")
      (node (ref "IC9") (pin "10") (pinfunction "1.6V_10") (pintype "bidirectional"))
    )
    (net (code "75") (name "unconnected-(IC9-50MV-Pad4)") (class "Default")
      (node (ref "IC9") (pin "4") (pinfunction "50MV_4") (pintype "bidirectional"))
    )
    (net (code "76") (name "unconnected-(IC9-800MV-Pad9)") (class "Default")
      (node (ref "IC9") (pin "9") (pinfunction "800MV_9") (pintype "bidirectional"))
    )
    (net (code "77") (name "unconnected-(IC9-FB-Pad2)") (class "Default")
      (node (ref "IC9") (pin "2") (pinfunction "FB_2") (pintype "bidirectional"))
    )
    (net (code "78") (name "unconnected-(IC9-SS-Pad11)") (class "Default")
      (node (ref "IC9") (pin "11") (pinfunction "SS_11") (pintype "bidirectional"))
    )
    (net (code "79") (name "unconnected-(IC10-ENA-Pad5)") (class "Default")
      (node (ref "IC10") (pin "5") (pinfunction "ENA_5") (pintype "bidirectional"))
    )
    (net (code "80") (name "unconnected-(IC10-NC_1-Pad2)") (class "Default")
      (node (ref "IC10") (pin "2") (pinfunction "NC_1_2") (pintype "bidirectional"))
    )
    (net (code "81") (name "unconnected-(IC10-NC_2-Pad3)") (class "Default")
      (node (ref "IC10") (pin "3") (pinfunction "NC_2_3") (pintype "bidirectional"))
    )
    (net (code "82") (name "unconnected-(IC11-1.6V-Pad10)") (class "Default")
      (node (ref "IC11") (pin "10") (pinfunction "1.6V_10") (pintype "bidirectional"))
    )
    (net (code "83") (name "unconnected-(IC11-50MV-Pad4)") (class "Default")
      (node (ref "IC11") (pin "4") (pinfunction "50MV_4") (pintype "bidirectional"))
    )
    (net (code "84") (name "unconnected-(IC11-100MV-Pad5)") (class "Default")
      (node (ref "IC11") (pin "5") (pinfunction "100MV_5") (pintype "bidirectional"))
    )
    (net (code "85") (name "unconnected-(IC11-FB-Pad2)") (class "Default")
      (node (ref "IC11") (pin "2") (pinfunction "FB_2") (pintype "bidirectional"))
    )
    (net (code "86") (name "unconnected-(IC11-SS-Pad11)") (class "Default")
      (node (ref "IC11") (pin "11") (pinfunction "SS_11") (pintype "bidirectional"))
    )
    (net (code "87") (name "unconnected-(IC12-50MV-Pad4)") (class "Default")
      (node (ref "IC12") (pin "4") (pinfunction "50MV_4") (pintype "bidirectional"))
    )
    (net (code "88") (name "unconnected-(IC12-100MV-Pad5)") (class "Default")
      (node (ref "IC12") (pin "5") (pinfunction "100MV_5") (pintype "bidirectional"))
    )
    (net (code "89") (name "unconnected-(IC12-200MV-Pad6)") (class "Default")
      (node (ref "IC12") (pin "6") (pinfunction "200MV_6") (pintype "bidirectional"))
    )
    (net (code "90") (name "unconnected-(IC12-800MV-Pad9)") (class "Default")
      (node (ref "IC12") (pin "9") (pinfunction "800MV_9") (pintype "bidirectional"))
    )
    (net (code "91") (name "unconnected-(IC12-FB-Pad2)") (class "Default")
      (node (ref "IC12") (pin "2") (pinfunction "FB_2") (pintype "bidirectional"))
    )
    (net (code "92") (name "unconnected-(IC12-SS-Pad11)") (class "Default")
      (node (ref "IC12") (pin "11") (pinfunction "SS_11") (pintype "bidirectional"))
    )
    (net (code "93") (name "unconnected-(IC14-50MV-Pad4)") (class "Default")
      (node (ref "IC14") (pin "4") (pinfunction "50MV_4") (pintype "bidirectional"))
    )
    (net (code "94") (name "unconnected-(IC14-100MV-Pad5)") (class "Default")
      (node (ref "IC14") (pin "5") (pinfunction "100MV_5") (pintype "bidirectional"))
    )
    (net (code "95") (name "unconnected-(IC14-200MV-Pad6)") (class "Default")
      (node (ref "IC14") (pin "6") (pinfunction "200MV_6") (pintype "bidirectional"))
    )
    (net (code "96") (name "unconnected-(IC14-800MV-Pad9)") (class "Default")
      (node (ref "IC14") (pin "9") (pinfunction "800MV_9") (pintype "bidirectional"))
    )
    (net (code "97") (name "unconnected-(IC14-FB-Pad2)") (class "Default")
      (node (ref "IC14") (pin "2") (pinfunction "FB_2") (pintype "bidirectional"))
    )
    (net (code "98") (name "unconnected-(IC14-SS-Pad11)") (class "Default")
      (node (ref "IC14") (pin "11") (pinfunction "SS_11") (pintype "bidirectional"))
    )
  )
)
